# 2_channel_DIP.net
KiCad netlist of a schematic drawn in EAGLE
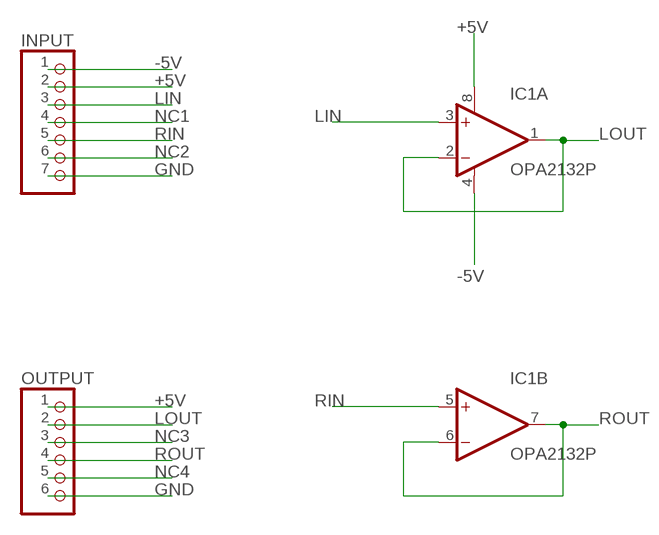
[diagram p0: schematic, sheet 1]

(export (version "E")
  (design (tool "Eeschema 10.0.6"))
  (components
    (comp (ref "IC1")
      (value "OPA2132P")
      (footprint "eagle-import:DIL08")
      (libsource (lib "eagle-import") (part "OPA2132P"))
    )
    (comp (ref "INPUT")
      (value "PINHD-1X7")
      (footprint "eagle-import:1X07")
      (libsource (lib "eagle-import") (part "PINHD-1X7"))
    )
    (comp (ref "OUTPUT")
      (value "PINHD-1X6")
      (footprint "eagle-import:1X06")
      (libsource (lib "eagle-import") (part "PINHD-1X6"))
    )
  )
  (nets
    (net (code "1") (name "/+5V") (class "Default")
      (node (ref "IC1") (pin "8") (pinfunction "V+_8") (pintype "power_in"))
      (node (ref "INPUT") (pin "2") (pinfunction "2_2") (pintype "passive"))
      (node (ref "OUTPUT") (pin "1") (pinfunction "1_1") (pintype "passive"))
    )
    (net (code "2") (name "/-5V") (class "Default")
      (node (ref "IC1") (pin "4") (pinfunction "V-_4") (pintype "power_in"))
      (node (ref "INPUT") (pin "1") (pinfunction "1_1") (pintype "passive"))
    )
    (net (code "3") (name "/GND") (class "Default")
      (node (ref "INPUT") (pin "7") (pinfunction "7_7") (pintype "passive"))
      (node (ref "OUTPUT") (pin "6") (pinfunction "6_6") (pintype "passive"))
    )
    (net (code "4") (name "/LIN") (class "Default")
      (node (ref "IC1") (pin "3") (pinfunction "+IN_3") (pintype "input"))
      (node (ref "INPUT") (pin "3") (pinfunction "3_3") (pintype "passive"))
    )
    (net (code "5") (name "/LOUT") (class "Default")
      (node (ref "IC1") (pin "1") (pinfunction "OUT_1") (pintype "output"))
      (node (ref "IC1") (pin "2") (pinfunction "-IN_2") (pintype "input"))
      (node (ref "OUTPUT") (pin "2") (pinfunction "2_2") (pintype "passive"))
    )
    (net (code "6") (name "/NC1") (class "Default")
      (node (ref "INPUT") (pin "4") (pinfunction "4_4") (pintype "passive"))
    )
    (net (code "7") (name "/NC2") (class "Default")
      (node (ref "INPUT") (pin "6") (pinfunction "6_6") (pintype "passive"))
    )
    (net (code "8") (name "/NC3") (class "Default")
      (node (ref "OUTPUT") (pin "3") (pinfunction "3_3") (pintype "passive"))
    )
    (net (code "9") (name "/NC4") (class "Default")
      (node (ref "OUTPUT") (pin "5") (pinfunction "5_5") (pintype "passive"))
    )
    (net (code "10") (name "/RIN") (class "Default")
      (node (ref "IC1") (pin "5") (pinfunction "+IN_5") (pintype "input"))
      (node (ref "INPUT") (pin "5") (pinfunction "5_5") (pintype "passive"))
    )
    (net (code "11") (name "/ROUT") (class "Default")
      (node (ref "IC1") (pin "6") (pinfunction "-IN_6") (pintype "input"))
      (node (ref "IC1") (pin "7") (pinfunction "OUT_7") (pintype "output"))
      (node (ref "OUTPUT") (pin "4") (pinfunction "4_4") (pintype "passive"))
    )
  )
)
